# Rapide328smd.net
KiCad netlist of a schematic drawn in EAGLE
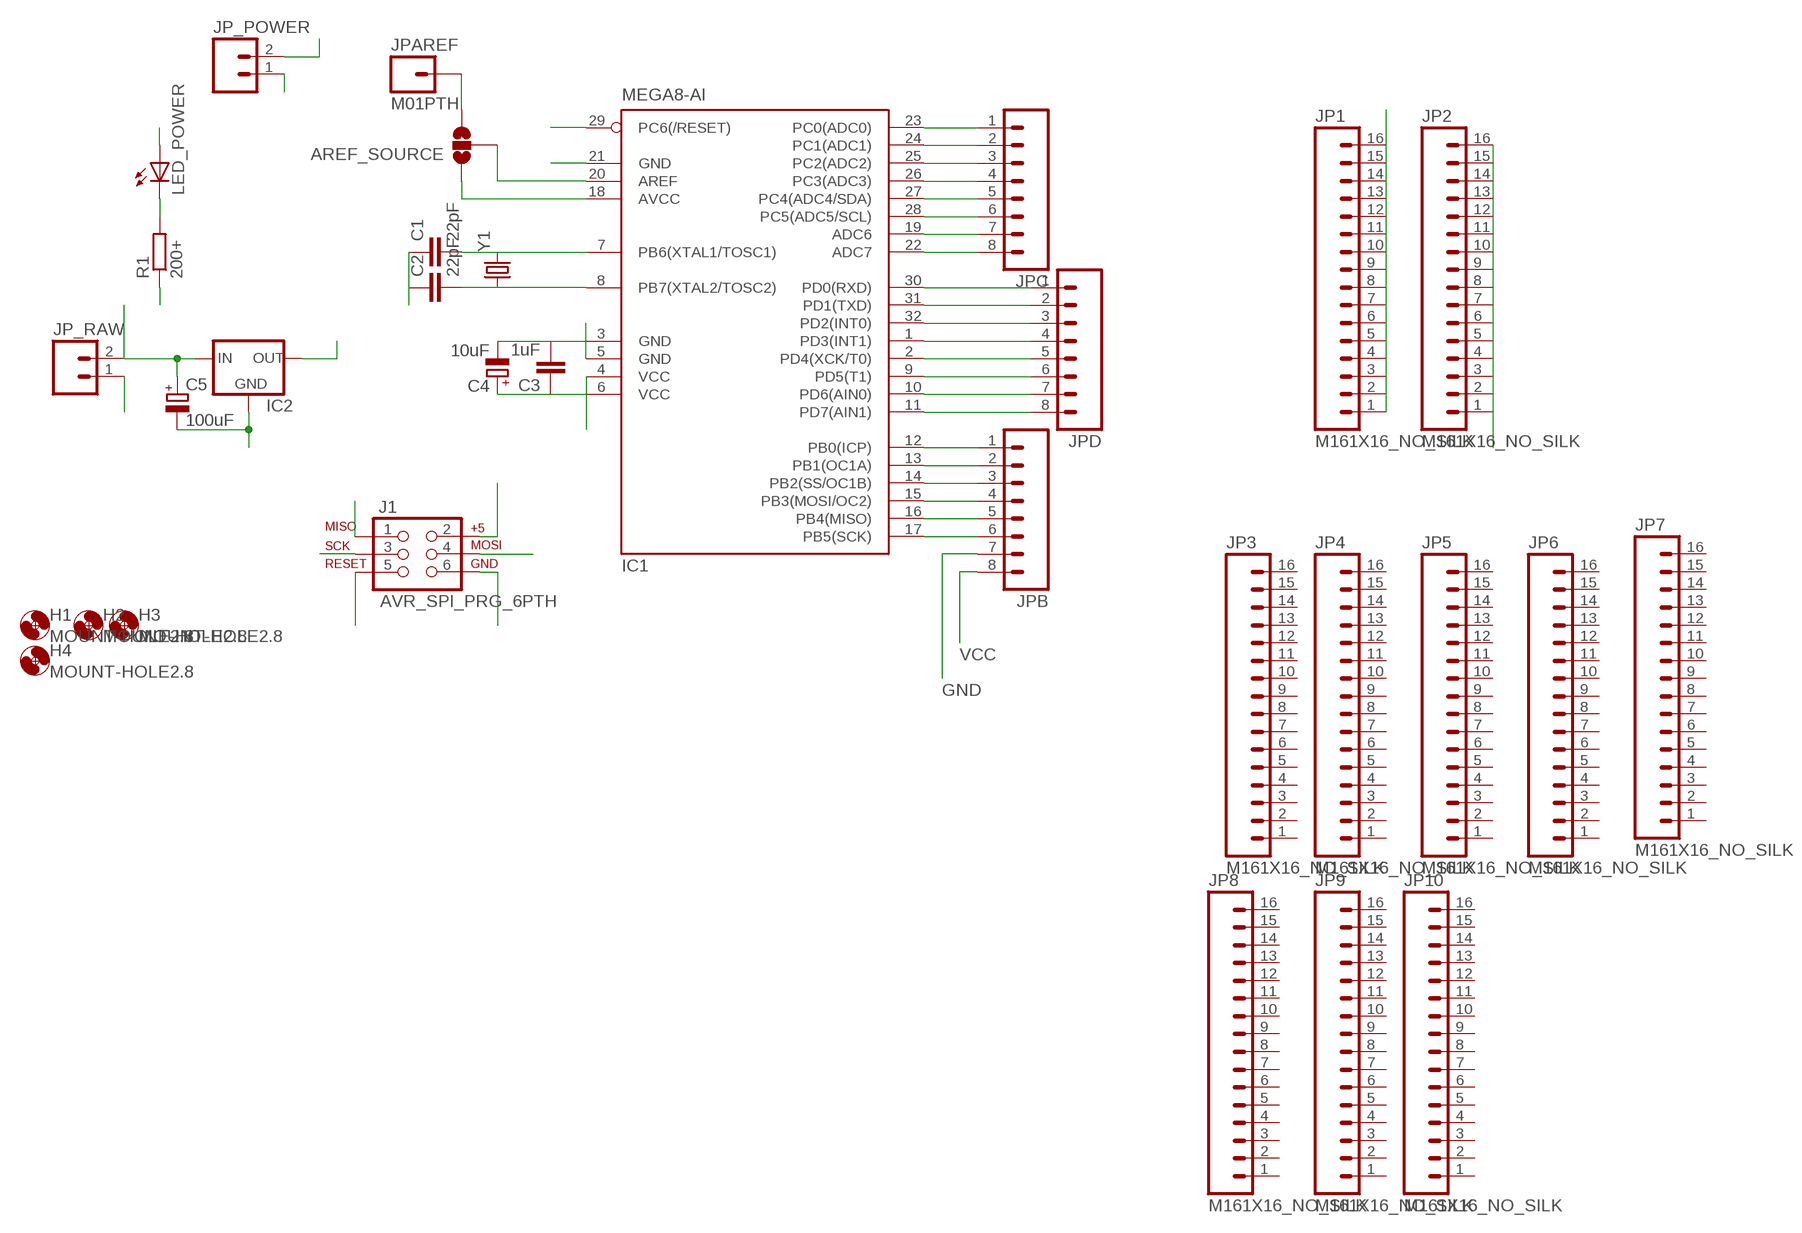
[diagram p0: schematic, sheet 1]

(export (version "E")
  (design (tool "Eeschema 10.0.6"))
  (components
    (comp (ref "AREF_SOURCE")
      (value "SOLDERJUMPER_2WAYPASTE1&2")
      (footprint "eagle-import:SJ_3_PASTE1&2")
      (libsource (lib "eagle-import") (part "SOLDERJUMPER_2WAYPASTE1&2"))
    )
    (comp (ref "C1")
      (value "22pF")
      (footprint "eagle-import:C025-024X044")
      (libsource (lib "eagle-import") (part "C-EU025-024X044"))
    )
    (comp (ref "C2")
      (value "22pF")
      (footprint "eagle-import:C025-024X044")
      (libsource (lib "eagle-import") (part "C-EU025-024X044"))
    )
    (comp (ref "C3")
      (value "1uF")
      (footprint "eagle-import:C025-024X044")
      (libsource (lib "eagle-import") (part "C-EU025-024X044"))
    )
    (comp (ref "C4")
      (value "10uF")
      (footprint "eagle-import:E2-5")
      (libsource (lib "eagle-import") (part "CPOL-EUE2-5"))
    )
    (comp (ref "C5")
      (value "100uF")
      (footprint "eagle-import:E2-5")
      (libsource (lib "eagle-import") (part "CPOL-EUE2-5"))
    )
    (comp (ref "H1")
      (value "MOUNT-HOLE2.8")
      (footprint "eagle-import:2,8")
      (libsource (lib "eagle-import") (part "MOUNT-HOLE2.8"))
    )
    (comp (ref "H2")
      (value "MOUNT-HOLE2.8")
      (footprint "eagle-import:2,8")
      (libsource (lib "eagle-import") (part "MOUNT-HOLE2.8"))
    )
    (comp (ref "H3")
      (value "MOUNT-HOLE2.8")
      (footprint "eagle-import:2,8")
      (libsource (lib "eagle-import") (part "MOUNT-HOLE2.8"))
    )
    (comp (ref "H4")
      (value "MOUNT-HOLE2.8")
      (footprint "eagle-import:2,8")
      (libsource (lib "eagle-import") (part "MOUNT-HOLE2.8"))
    )
    (comp (ref "IC1")
      (value "MEGA8-AI")
      (footprint "eagle-import:TQFP32-08")
      (fields (field (name "MPN") "ATMEGA8-16AU"))
      (libsource (lib "eagle-import") (part "MEGA8-AI"))
    )
    (comp (ref "IC2")
      (value "V_REG_78XXSINK")
      (footprint "eagle-import:TO220-IGO")
      (libsource (lib "eagle-import") (part "V_REG_78XXSINK"))
    )
    (comp (ref "J1")
      (value "AVR_SPI_PRG_6PTH")
      (footprint "eagle-import:2X3")
      (libsource (lib "eagle-import") (part "AVR_SPI_PRG_6PTH"))
    )
    (comp (ref "JP1")
      (value "M161X16_NO_SILK")
      (footprint "eagle-import:1X16_NO_SILK")
      (libsource (lib "eagle-import") (part "M161X16_NO_SILK"))
    )
    (comp (ref "JP2")
      (value "M161X16_NO_SILK")
      (footprint "eagle-import:1X16_NO_SILK")
      (libsource (lib "eagle-import") (part "M161X16_NO_SILK"))
    )
    (comp (ref "JP3")
      (value "M161X16_NO_SILK")
      (footprint "eagle-import:1X16_NO_SILK")
      (libsource (lib "eagle-import") (part "M161X16_NO_SILK"))
    )
    (comp (ref "JP4")
      (value "M161X16_NO_SILK")
      (footprint "eagle-import:1X16_NO_SILK")
      (libsource (lib "eagle-import") (part "M161X16_NO_SILK"))
    )
    (comp (ref "JP5")
      (value "M161X16_NO_SILK")
      (footprint "eagle-import:1X16_NO_SILK")
      (libsource (lib "eagle-import") (part "M161X16_NO_SILK"))
    )
    (comp (ref "JP6")
      (value "M161X16_NO_SILK")
      (footprint "eagle-import:1X16_NO_SILK")
      (libsource (lib "eagle-import") (part "M161X16_NO_SILK"))
    )
    (comp (ref "JP7")
      (value "M161X16_NO_SILK")
      (footprint "eagle-import:1X16_NO_SILK")
      (libsource (lib "eagle-import") (part "M161X16_NO_SILK"))
    )
    (comp (ref "JP8")
      (value "M161X16_NO_SILK")
      (footprint "eagle-import:1X16_NO_SILK")
      (libsource (lib "eagle-import") (part "M161X16_NO_SILK"))
    )
    (comp (ref "JP9")
      (value "M161X16_NO_SILK")
      (footprint "eagle-import:1X16_NO_SILK")
      (libsource (lib "eagle-import") (part "M161X16_NO_SILK"))
    )
    (comp (ref "JP10")
      (value "M161X16_NO_SILK")
      (footprint "eagle-import:1X16_NO_SILK")
      (libsource (lib "eagle-import") (part "M161X16_NO_SILK"))
    )
    (comp (ref "JPAREF")
      (value "M01PTH")
      (footprint "eagle-import:1X01")
      (libsource (lib "eagle-import") (part "M01PTH"))
    )
    (comp (ref "JPB")
      (value "M081X08")
      (footprint "eagle-import:1X08")
      (libsource (lib "eagle-import") (part "M081X08"))
    )
    (comp (ref "JPC")
      (value "M081X08")
      (footprint "eagle-import:1X08")
      (libsource (lib "eagle-import") (part "M081X08"))
    )
    (comp (ref "JPD")
      (value "M081X08")
      (footprint "eagle-import:1X08")
      (libsource (lib "eagle-import") (part "M081X08"))
    )
    (comp (ref "JP_POWER")
      (value "M02PTH3")
      (footprint "eagle-import:1X02_LONGPADS")
      (libsource (lib "eagle-import") (part "M02PTH3"))
    )
    (comp (ref "JP_RAW")
      (value "M02PTH3")
      (footprint "eagle-import:1X02_LONGPADS")
      (libsource (lib "eagle-import") (part "M02PTH3"))
    )
    (comp (ref "LED_POWER")
      (value "LEDKA-3528ASYC")
      (footprint "eagle-import:KA-3528ASYC")
      (libsource (lib "eagle-import") (part "LEDKA-3528ASYC"))
    )
    (comp (ref "R1")
      (value "200+")
      (footprint "eagle-import:0204_7")
      (libsource (lib "eagle-import") (part "R-EU_0204/7"))
    )
    (comp (ref "Y1")
      (value "CRYSTALHC49UV")
      (footprint "eagle-import:HC49U-V")
      (libsource (lib "eagle-import") (part "CRYSTALHC49UV"))
    )
  )
  (nets
    (net (code "1") (name "/GND") (class "Default")
      (node (ref "C1") (pin "1") (pinfunction "1_1") (pintype "passive"))
      (node (ref "C2") (pin "1") (pinfunction "1_1") (pintype "passive"))
      (node (ref "C3") (pin "2") (pinfunction "2_2") (pintype "passive"))
      (node (ref "C4") (pin "-") (pinfunction "-_-") (pintype "passive"))
      (node (ref "C5") (pin "-") (pinfunction "-_-") (pintype "passive"))
      (node (ref "IC1") (pin "21") (pinfunction "GND_21") (pintype "power_in"))
      (node (ref "IC1") (pin "3") (pinfunction "GND_3") (pintype "power_in"))
      (node (ref "IC1") (pin "5") (pinfunction "GND_5") (pintype "power_in"))
      (node (ref "IC2") (pin "GND") (pinfunction "GND_GND") (pintype "input"))
      (node (ref "J1") (pin "6") (pinfunction "6_6") (pintype "passive"))
      (node (ref "JP2") (pin "1") (pinfunction "1_1") (pintype "passive"))
      (node (ref "JP2") (pin "10") (pinfunction "10_10") (pintype "passive"))
      (node (ref "JP2") (pin "11") (pinfunction "11_11") (pintype "passive"))
      (node (ref "JP2") (pin "12") (pinfunction "12_12") (pintype "passive"))
      (node (ref "JP2") (pin "13") (pinfunction "13_13") (pintype "passive"))
      (node (ref "JP2") (pin "14") (pinfunction "14_14") (pintype "passive"))
      (node (ref "JP2") (pin "15") (pinfunction "15_15") (pintype "passive"))
      (node (ref "JP2") (pin "16") (pinfunction "16_16") (pintype "passive"))
      (node (ref "JP2") (pin "2") (pinfunction "2_2") (pintype "passive"))
      (node (ref "JP2") (pin "3") (pinfunction "3_3") (pintype "passive"))
      (node (ref "JP2") (pin "4") (pinfunction "4_4") (pintype "passive"))
      (node (ref "JP2") (pin "5") (pinfunction "5_5") (pintype "passive"))
      (node (ref "JP2") (pin "6") (pinfunction "6_6") (pintype "passive"))
      (node (ref "JP2") (pin "7") (pinfunction "7_7") (pintype "passive"))
      (node (ref "JP2") (pin "8") (pinfunction "8_8") (pintype "passive"))
      (node (ref "JP2") (pin "9") (pinfunction "9_9") (pintype "passive"))
      (node (ref "JPB") (pin "7") (pinfunction "7_7") (pintype "passive"))
      (node (ref "JP_POWER") (pin "1") (pinfunction "1_1") (pintype "passive"))
      (node (ref "JP_RAW") (pin "1") (pinfunction "1_1") (pintype "passive"))
      (node (ref "R1") (pin "1") (pinfunction "1_1") (pintype "passive"))
    )
    (net (code "2") (name "/MISO") (class "Default")
      (node (ref "IC1") (pin "16") (pinfunction "PB4(MISO)_16") (pintype "bidirectional"))
      (node (ref "J1") (pin "1") (pinfunction "1_1") (pintype "passive"))
      (node (ref "JPB") (pin "5") (pinfunction "5_5") (pintype "passive"))
    )
    (net (code "3") (name "/MOSI") (class "Default")
      (node (ref "IC1") (pin "15") (pinfunction "PB3(MOSI/OC2)_15") (pintype "bidirectional"))
      (node (ref "J1") (pin "4") (pinfunction "4_4") (pintype "passive"))
      (node (ref "JPB") (pin "4") (pinfunction "4_4") (pintype "passive"))
    )
    (net (code "4") (name "/RESET") (class "Default")
      (node (ref "IC1") (pin "29") (pinfunction "PC6(/RESET)_29") (pintype "bidirectional"))
      (node (ref "J1") (pin "5") (pinfunction "5_5") (pintype "passive"))
    )
    (net (code "5") (name "/SCK") (class "Default")
      (node (ref "IC1") (pin "17") (pinfunction "PB5(SCK)_17") (pintype "bidirectional"))
      (node (ref "J1") (pin "3") (pinfunction "3_3") (pintype "passive"))
      (node (ref "JPB") (pin "6") (pinfunction "6_6") (pintype "passive"))
    )
    (net (code "6") (name "/VCC") (class "Default")
      (node (ref "AREF_SOURCE") (pin "1") (pinfunction "1_1") (pintype "passive"))
      (node (ref "C3") (pin "1") (pinfunction "1_1") (pintype "passive"))
      (node (ref "C4") (pin "+") (pinfunction "+_+") (pintype "passive"))
      (node (ref "IC1") (pin "18") (pinfunction "AVCC_18") (pintype "power_in"))
      (node (ref "IC1") (pin "4") (pinfunction "VCC_4") (pintype "power_in"))
      (node (ref "IC1") (pin "6") (pinfunction "VCC_6") (pintype "power_in"))
      (node (ref "IC2") (pin "OUT") (pinfunction "OUT_OUT") (pintype "output"))
      (node (ref "J1") (pin "2") (pinfunction "2_2") (pintype "passive"))
      (node (ref "JP1") (pin "1") (pinfunction "1_1") (pintype "passive"))
      (node (ref "JP1") (pin "10") (pinfunction "10_10") (pintype "passive"))
      (node (ref "JP1") (pin "11") (pinfunction "11_11") (pintype "passive"))
      (node (ref "JP1") (pin "12") (pinfunction "12_12") (pintype "passive"))
      (node (ref "JP1") (pin "13") (pinfunction "13_13") (pintype "passive"))
      (node (ref "JP1") (pin "14") (pinfunction "14_14") (pintype "passive"))
      (node (ref "JP1") (pin "15") (pinfunction "15_15") (pintype "passive"))
      (node (ref "JP1") (pin "16") (pinfunction "16_16") (pintype "passive"))
      (node (ref "JP1") (pin "2") (pinfunction "2_2") (pintype "passive"))
      (node (ref "JP1") (pin "3") (pinfunction "3_3") (pintype "passive"))
      (node (ref "JP1") (pin "4") (pinfunction "4_4") (pintype "passive"))
      (node (ref "JP1") (pin "5") (pinfunction "5_5") (pintype "passive"))
      (node (ref "JP1") (pin "6") (pinfunction "6_6") (pintype "passive"))
      (node (ref "JP1") (pin "7") (pinfunction "7_7") (pintype "passive"))
      (node (ref "JP1") (pin "8") (pinfunction "8_8") (pintype "passive"))
      (node (ref "JP1") (pin "9") (pinfunction "9_9") (pintype "passive"))
      (node (ref "JPB") (pin "8") (pinfunction "8_8") (pintype "passive"))
      (node (ref "JP_POWER") (pin "2") (pinfunction "2_2") (pintype "passive"))
      (node (ref "LED_POWER") (pin "A") (pinfunction "A_A") (pintype "passive"))
    )
    (net (code "7") (name "Net-(AREF_SOURCE-Pad3)") (class "Default")
      (node (ref "AREF_SOURCE") (pin "3") (pinfunction "3_3") (pintype "passive"))
      (node (ref "JPAREF") (pin "1") (pinfunction "1_1") (pintype "passive"))
    )
    (net (code "8") (name "Net-(C5-Pad+)") (class "Default")
      (node (ref "C5") (pin "+") (pinfunction "+_+") (pintype "passive"))
      (node (ref "IC2") (pin "IN") (pinfunction "IN_IN") (pintype "input"))
      (node (ref "JP_RAW") (pin "2") (pinfunction "2_2") (pintype "passive"))
    )
    (net (code "9") (name "Net-(IC1-ADC6)") (class "Default")
      (node (ref "IC1") (pin "19") (pinfunction "ADC6_19") (pintype "bidirectional"))
      (node (ref "JPC") (pin "7") (pinfunction "7_7") (pintype "passive"))
    )
    (net (code "10") (name "Net-(IC1-ADC7)") (class "Default")
      (node (ref "IC1") (pin "22") (pinfunction "ADC7_22") (pintype "bidirectional"))
      (node (ref "JPC") (pin "8") (pinfunction "8_8") (pintype "passive"))
    )
    (net (code "11") (name "Net-(IC1-AREF)") (class "Default")
      (node (ref "AREF_SOURCE") (pin "2") (pinfunction "2_2") (pintype "passive"))
      (node (ref "IC1") (pin "20") (pinfunction "AREF_20") (pintype "passive"))
    )
    (net (code "12") (name "Net-(IC1-PB0(ICP))") (class "Default")
      (node (ref "IC1") (pin "12") (pinfunction "PB0(ICP)_12") (pintype "bidirectional"))
      (node (ref "JPB") (pin "1") (pinfunction "1_1") (pintype "passive"))
    )
    (net (code "13") (name "Net-(IC1-PB1(OC1A))") (class "Default")
      (node (ref "IC1") (pin "13") (pinfunction "PB1(OC1A)_13") (pintype "bidirectional"))
      (node (ref "JPB") (pin "2") (pinfunction "2_2") (pintype "passive"))
    )
    (net (code "14") (name "Net-(IC1-PB2(SS{slash}OC1B))") (class "Default")
      (node (ref "IC1") (pin "14") (pinfunction "PB2(SS/OC1B)_14") (pintype "bidirectional"))
      (node (ref "JPB") (pin "3") (pinfunction "3_3") (pintype "passive"))
    )
    (net (code "15") (name "Net-(IC1-PB6(XTAL1{slash}TOSC1))") (class "Default")
      (node (ref "C1") (pin "2") (pinfunction "2_2") (pintype "passive"))
      (node (ref "IC1") (pin "7") (pinfunction "PB6(XTAL1/TOSC1)_7") (pintype "bidirectional"))
      (node (ref "Y1") (pin "2") (pinfunction "2_2") (pintype "passive"))
    )
    (net (code "16") (name "Net-(IC1-PB7(XTAL2{slash}TOSC2))") (class "Default")
      (node (ref "C2") (pin "2") (pinfunction "2_2") (pintype "passive"))
      (node (ref "IC1") (pin "8") (pinfunction "PB7(XTAL2/TOSC2)_8") (pintype "bidirectional"))
      (node (ref "Y1") (pin "1") (pinfunction "1_1") (pintype "passive"))
    )
    (net (code "17") (name "Net-(IC1-PC0(ADC0))") (class "Default")
      (node (ref "IC1") (pin "23") (pinfunction "PC0(ADC0)_23") (pintype "bidirectional"))
      (node (ref "JPC") (pin "1") (pinfunction "1_1") (pintype "passive"))
    )
    (net (code "18") (name "Net-(IC1-PC1(ADC1))") (class "Default")
      (node (ref "IC1") (pin "24") (pinfunction "PC1(ADC1)_24") (pintype "bidirectional"))
      (node (ref "JPC") (pin "2") (pinfunction "2_2") (pintype "passive"))
    )
    (net (code "19") (name "Net-(IC1-PC2(ADC2))") (class "Default")
      (node (ref "IC1") (pin "25") (pinfunction "PC2(ADC2)_25") (pintype "bidirectional"))
      (node (ref "JPC") (pin "3") (pinfunction "3_3") (pintype "passive"))
    )
    (net (code "20") (name "Net-(IC1-PC3(ADC3))") (class "Default")
      (node (ref "IC1") (pin "26") (pinfunction "PC3(ADC3)_26") (pintype "bidirectional"))
      (node (ref "JPC") (pin "4") (pinfunction "4_4") (pintype "passive"))
    )
    (net (code "21") (name "Net-(IC1-PC4(ADC4{slash}SDA))") (class "Default")
      (node (ref "IC1") (pin "27") (pinfunction "PC4(ADC4/SDA)_27") (pintype "bidirectional"))
      (node (ref "JPC") (pin "5") (pinfunction "5_5") (pintype "passive"))
    )
    (net (code "22") (name "Net-(IC1-PC5(ADC5{slash}SCL))") (class "Default")
      (node (ref "IC1") (pin "28") (pinfunction "PC5(ADC5/SCL)_28") (pintype "bidirectional"))
      (node (ref "JPC") (pin "6") (pinfunction "6_6") (pintype "passive"))
    )
    (net (code "23") (name "Net-(IC1-PD0(RXD))") (class "Default")
      (node (ref "IC1") (pin "30") (pinfunction "PD0(RXD)_30") (pintype "bidirectional"))
      (node (ref "JPD") (pin "1") (pinfunction "1_1") (pintype "passive"))
    )
    (net (code "24") (name "Net-(IC1-PD1(TXD))") (class "Default")
      (node (ref "IC1") (pin "31") (pinfunction "PD1(TXD)_31") (pintype "bidirectional"))
      (node (ref "JPD") (pin "2") (pinfunction "2_2") (pintype "passive"))
    )
    (net (code "25") (name "Net-(IC1-PD2(INT0))") (class "Default")
      (node (ref "IC1") (pin "32") (pinfunction "PD2(INT0)_32") (pintype "bidirectional"))
      (node (ref "JPD") (pin "3") (pinfunction "3_3") (pintype "passive"))
    )
    (net (code "26") (name "Net-(IC1-PD3(INT1))") (class "Default")
      (node (ref "IC1") (pin "1") (pinfunction "PD3(INT1)_1") (pintype "bidirectional"))
      (node (ref "JPD") (pin "4") (pinfunction "4_4") (pintype "passive"))
    )
    (net (code "27") (name "Net-(IC1-PD4(XCK{slash}T0))") (class "Default")
      (node (ref "IC1") (pin "2") (pinfunction "PD4(XCK/T0)_2") (pintype "bidirectional"))
      (node (ref "JPD") (pin "5") (pinfunction "5_5") (pintype "passive"))
    )
    (net (code "28") (name "Net-(IC1-PD5(T1))") (class "Default")
      (node (ref "IC1") (pin "9") (pinfunction "PD5(T1)_9") (pintype "bidirectional"))
      (node (ref "JPD") (pin "6") (pinfunction "6_6") (pintype "passive"))
    )
    (net (code "29") (name "Net-(IC1-PD6(AIN0))") (class "Default")
      (node (ref "IC1") (pin "10") (pinfunction "PD6(AIN0)_10") (pintype "bidirectional"))
      (node (ref "JPD") (pin "7") (pinfunction "7_7") (pintype "passive"))
    )
    (net (code "30") (name "Net-(IC1-PD7(AIN1))") (class "Default")
      (node (ref "IC1") (pin "11") (pinfunction "PD7(AIN1)_11") (pintype "bidirectional"))
      (node (ref "JPD") (pin "8") (pinfunction "8_8") (pintype "passive"))
    )
    (net (code "31") (name "Net-(LED_POWER-PadC)") (class "Default")
      (node (ref "LED_POWER") (pin "C") (pinfunction "C_C") (pintype "passive"))
      (node (ref "R1") (pin "2") (pinfunction "2_2") (pintype "passive"))
    )
    (net (code "32") (name "unconnected-(JP3-Pad1)") (class "Default")
      (node (ref "JP3") (pin "1") (pinfunction "1_1") (pintype "passive"))
    )
    (net (code "33") (name "unconnected-(JP3-Pad2)") (class "Default")
      (node (ref "JP3") (pin "2") (pinfunction "2_2") (pintype "passive"))
    )
    (net (code "34") (name "unconnected-(JP3-Pad3)") (class "Default")
      (node (ref "JP3") (pin "3") (pinfunction "3_3") (pintype "passive"))
    )
    (net (code "35") (name "unconnected-(JP3-Pad4)") (class "Default")
      (node (ref "JP3") (pin "4") (pinfunction "4_4") (pintype "passive"))
    )
    (net (code "36") (name "unconnected-(JP3-Pad5)") (class "Default")
      (node (ref "JP3") (pin "5") (pinfunction "5_5") (pintype "passive"))
    )
    (net (code "37") (name "unconnected-(JP3-Pad6)") (class "Default")
      (node (ref "JP3") (pin "6") (pinfunction "6_6") (pintype "passive"))
    )
    (net (code "38") (name "unconnected-(JP3-Pad7)") (class "Default")
      (node (ref "JP3") (pin "7") (pinfunction "7_7") (pintype "passive"))
    )
    (net (code "39") (name "unconnected-(JP3-Pad8)") (class "Default")
      (node (ref "JP3") (pin "8") (pinfunction "8_8") (pintype "passive"))
    )
    (net (code "40") (name "unconnected-(JP3-Pad9)") (class "Default")
      (node (ref "JP3") (pin "9") (pinfunction "9_9") (pintype "passive"))
    )
    (net (code "41") (name "unconnected-(JP3-Pad10)") (class "Default")
      (node (ref "JP3") (pin "10") (pinfunction "10_10") (pintype "passive"))
    )
    (net (code "42") (name "unconnected-(JP3-Pad11)") (class "Default")
      (node (ref "JP3") (pin "11") (pinfunction "11_11") (pintype "passive"))
    )
    (net (code "43") (name "unconnected-(JP3-Pad12)") (class "Default")
      (node (ref "JP3") (pin "12") (pinfunction "12_12") (pintype "passive"))
    )
    (net (code "44") (name "unconnected-(JP3-Pad13)") (class "Default")
      (node (ref "JP3") (pin "13") (pinfunction "13_13") (pintype "passive"))
    )
    (net (code "45") (name "unconnected-(JP3-Pad14)") (class "Default")
      (node (ref "JP3") (pin "14") (pinfunction "14_14") (pintype "passive"))
    )
    (net (code "46") (name "unconnected-(JP3-Pad15)") (class "Default")
      (node (ref "JP3") (pin "15") (pinfunction "15_15") (pintype "passive"))
    )
    (net (code "47") (name "unconnected-(JP3-Pad16)") (class "Default")
      (node (ref "JP3") (pin "16") (pinfunction "16_16") (pintype "passive"))
    )
    (net (code "48") (name "unconnected-(JP4-Pad1)") (class "Default")
      (node (ref "JP4") (pin "1") (pinfunction "1_1") (pintype "passive"))
    )
    (net (code "49") (name "unconnected-(JP4-Pad2)") (class "Default")
      (node (ref "JP4") (pin "2") (pinfunction "2_2") (pintype "passive"))
    )
    (net (code "50") (name "unconnected-(JP4-Pad3)") (class "Default")
      (node (ref "JP4") (pin "3") (pinfunction "3_3") (pintype "passive"))
    )
    (net (code "51") (name "unconnected-(JP4-Pad4)") (class "Default")
      (node (ref "JP4") (pin "4") (pinfunction "4_4") (pintype "passive"))
    )
    (net (code "52") (name "unconnected-(JP4-Pad5)") (class "Default")
      (node (ref "JP4") (pin "5") (pinfunction "5_5") (pintype "passive"))
    )
    (net (code "53") (name "unconnected-(JP4-Pad6)") (class "Default")
      (node (ref "JP4") (pin "6") (pinfunction "6_6") (pintype "passive"))
    )
    (net (code "54") (name "unconnected-(JP4-Pad7)") (class "Default")
      (node (ref "JP4") (pin "7") (pinfunction "7_7") (pintype "passive"))
    )
    (net (code "55") (name "unconnected-(JP4-Pad8)") (class "Default")
      (node (ref "JP4") (pin "8") (pinfunction "8_8") (pintype "passive"))
    )
    (net (code "56") (name "unconnected-(JP4-Pad9)") (class "Default")
      (node (ref "JP4") (pin "9") (pinfunction "9_9") (pintype "passive"))
    )
    (net (code "57") (name "unconnected-(JP4-Pad10)") (class "Default")
      (node (ref "JP4") (pin "10") (pinfunction "10_10") (pintype "passive"))
    )
    (net (code "58") (name "unconnected-(JP4-Pad11)") (class "Default")
      (node (ref "JP4") (pin "11") (pinfunction "11_11") (pintype "passive"))
    )
    (net (code "59") (name "unconnected-(JP4-Pad12)") (class "Default")
      (node (ref "JP4") (pin "12") (pinfunction "12_12") (pintype "passive"))
    )
    (net (code "60") (name "unconnected-(JP4-Pad13)") (class "Default")
      (node (ref "JP4") (pin "13") (pinfunction "13_13") (pintype "passive"))
    )
    (net (code "61") (name "unconnected-(JP4-Pad14)") (class "Default")
      (node (ref "JP4") (pin "14") (pinfunction "14_14") (pintype "passive"))
    )
    (net (code "62") (name "unconnected-(JP4-Pad15)") (class "Default")
      (node (ref "JP4") (pin "15") (pinfunction "15_15") (pintype "passive"))
    )
    (net (code "63") (name "unconnected-(JP4-Pad16)") (class "Default")
      (node (ref "JP4") (pin "16") (pinfunction "16_16") (pintype "passive"))
    )
    (net (code "64") (name "unconnected-(JP5-Pad1)") (class "Default")
      (node (ref "JP5") (pin "1") (pinfunction "1_1") (pintype "passive"))
    )
    (net (code "65") (name "unconnected-(JP5-Pad2)") (class "Default")
      (node (ref "JP5") (pin "2") (pinfunction "2_2") (pintype "passive"))
    )
    (net (code "66") (name "unconnected-(JP5-Pad3)") (class "Default")
      (node (ref "JP5") (pin "3") (pinfunction "3_3") (pintype "passive"))
    )
    (net (code "67") (name "unconnected-(JP5-Pad4)") (class "Default")
      (node (ref "JP5") (pin "4") (pinfunction "4_4") (pintype "passive"))
    )
    (net (code "68") (name "unconnected-(JP5-Pad5)") (class "Default")
      (node (ref "JP5") (pin "5") (pinfunction "5_5") (pintype "passive"))
    )
    (net (code "69") (name "unconnected-(JP5-Pad6)") (class "Default")
      (node (ref "JP5") (pin "6") (pinfunction "6_6") (pintype "passive"))
    )
    (net (code "70") (name "unconnected-(JP5-Pad7)") (class "Default")
      (node (ref "JP5") (pin "7") (pinfunction "7_7") (pintype "passive"))
    )
    (net (code "71") (name "unconnected-(JP5-Pad8)") (class "Default")
      (node (ref "JP5") (pin "8") (pinfunction "8_8") (pintype "passive"))
    )
    (net (code "72") (name "unconnected-(JP5-Pad9)") (class "Default")
      (node (ref "JP5") (pin "9") (pinfunction "9_9") (pintype "passive"))
    )
    (net (code "73") (name "unconnected-(JP5-Pad10)") (class "Default")
      (node (ref "JP5") (pin "10") (pinfunction "10_10") (pintype "passive"))
    )
    (net (code "74") (name "unconnected-(JP5-Pad11)") (class "Default")
      (node (ref "JP5") (pin "11") (pinfunction "11_11") (pintype "passive"))
    )
    (net (code "75") (name "unconnected-(JP5-Pad12)") (class "Default")
      (node (ref "JP5") (pin "12") (pinfunction "12_12") (pintype "passive"))
    )
    (net (code "76") (name "unconnected-(JP5-Pad13)") (class "Default")
      (node (ref "JP5") (pin "13") (pinfunction "13_13") (pintype "passive"))
    )
    (net (code "77") (name "unconnected-(JP5-Pad14)") (class "Default")
      (node (ref "JP5") (pin "14") (pinfunction "14_14") (pintype "passive"))
    )
    (net (code "78") (name "unconnected-(JP5-Pad15)") (class "Default")
      (node (ref "JP5") (pin "15") (pinfunction "15_15") (pintype "passive"))
    )
    (net (code "79") (name "unconnected-(JP5-Pad16)") (class "Default")
      (node (ref "JP5") (pin "16") (pinfunction "16_16") (pintype "passive"))
    )
    (net (code "80") (name "unconnected-(JP6-Pad1)") (class "Default")
      (node (ref "JP6") (pin "1") (pinfunction "1_1") (pintype "passive"))
    )
    (net (code "81") (name "unconnected-(JP6-Pad2)") (class "Default")
      (node (ref "JP6") (pin "2") (pinfunction "2_2") (pintype "passive"))
    )
    (net (code "82") (name "unconnected-(JP6-Pad3)") (class "Default")
      (node (ref "JP6") (pin "3") (pinfunction "3_3") (pintype "passive"))
    )
    (net (code "83") (name "unconnected-(JP6-Pad4)") (class "Default")
      (node (ref "JP6") (pin "4") (pinfunction "4_4") (pintype "passive"))
    )
    (net (code "84") (name "unconnected-(JP6-Pad5)") (class "Default")
      (node (ref "JP6") (pin "5") (pinfunction "5_5") (pintype "passive"))
    )
    (net (code "85") (name "unconnected-(JP6-Pad6)") (class "Default")
      (node (ref "JP6") (pin "6") (pinfunction "6_6") (pintype "passive"))
    )
    (net (code "86") (name "unconnected-(JP6-Pad7)") (class "Default")
      (node (ref "JP6") (pin "7") (pinfunction "7_7") (pintype "passive"))
    )
    (net (code "87") (name "unconnected-(JP6-Pad8)") (class "Default")
      (node (ref "JP6") (pin "8") (pinfunction "8_8") (pintype "passive"))
    )
    (net (code "88") (name "unconnected-(JP6-Pad9)") (class "Default")
      (node (ref "JP6") (pin "9") (pinfunction "9_9") (pintype "passive"))
    )
    (net (code "89") (name "unconnected-(JP6-Pad10)") (class "Default")
      (node (ref "JP6") (pin "10") (pinfunction "10_10") (pintype "passive"))
    )
    (net (code "90") (name "unconnected-(JP6-Pad11)") (class "Default")
      (node (ref "JP6") (pin "11") (pinfunction "11_11") (pintype "passive"))
    )
    (net (code "91") (name "unconnected-(JP6-Pad12)") (class "Default")
      (node (ref "JP6") (pin "12") (pinfunction "12_12") (pintype "passive"))
    )
    (net (code "92") (name "unconnected-(JP6-Pad13)") (class "Default")
      (node (ref "JP6") (pin "13") (pinfunction "13_13") (pintype "passive"))
    )
    (net (code "93") (name "unconnected-(JP6-Pad14)") (class "Default")
      (node (ref "JP6") (pin "14") (pinfunction "14_14") (pintype "passive"))
    )
    (net (code "94") (name "unconnected-(JP6-Pad15)") (class "Default")
      (node (ref "JP6") (pin "15") (pinfunction "15_15") (pintype "passive"))
    )
    (net (code "95") (name "unconnected-(JP6-Pad16)") (class "Default")
      (node (ref "JP6") (pin "16") (pinfunction "16_16") (pintype "passive"))
    )
    (net (code "96") (name "unconnected-(JP7-Pad1)") (class "Default")
      (node (ref "JP7") (pin "1") (pinfunction "1_1") (pintype "passive"))
    )
    (net (code "97") (name "unconnected-(JP7-Pad2)") (class "Default")
      (node (ref "JP7") (pin "2") (pinfunction "2_2") (pintype "passive"))
    )
    (net (code "98") (name "unconnected-(JP7-Pad3)") (class "Default")
      (node (ref "JP7") (pin "3") (pinfunction "3_3") (pintype "passive"))
    )
    (net (code "99") (name "unconnected-(JP7-Pad4)") (class "Default")
      (node (ref "JP7") (pin "4") (pinfunction "4_4") (pintype "passive"))
    )
    (net (code "100") (name "unconnected-(JP7-Pad5)") (class "Default")
      (node (ref "JP7") (pin "5") (pinfunction "5_5") (pintype "passive"))
    )
    (net (code "101") (name "unconnected-(JP7-Pad6)") (class "Default")
      (node (ref "JP7") (pin "6") (pinfunction "6_6") (pintype "passive"))
    )
    (net (code "102") (name "unconnected-(JP7-Pad7)") (class "Default")
      (node (ref "JP7") (pin "7") (pinfunction "7_7") (pintype "passive"))
    )
    (net (code "103") (name "unconnected-(JP7-Pad8)") (class "Default")
      (node (ref "JP7") (pin "8") (pinfunction "8_8") (pintype "passive"))
    )
    (net (code "104") (name "unconnected-(JP7-Pad9)") (class "Default")
      (node (ref "JP7") (pin "9") (pinfunction "9_9") (pintype "passive"))
    )
    (net (code "105") (name "unconnected-(JP7-Pad10)") (class "Default")
      (node (ref "JP7") (pin "10") (pinfunction "10_10") (pintype "passive"))
    )
    (net (code "106") (name "unconnected-(JP7-Pad11)") (class "Default")
      (node (ref "JP7") (pin "11") (pinfunction "11_11") (pintype "passive"))
    )
    (net (code "107") (name "unconnected-(JP7-Pad12)") (class "Default")
      (node (ref "JP7") (pin "12") (pinfunction "12_12") (pintype "passive"))
    )
    (net (code "108") (name "unconnected-(JP7-Pad13)") (class "Default")
      (node (ref "JP7") (pin "13") (pinfunction "13_13") (pintype "passive"))
    )
    (net (code "109") (name "unconnected-(JP7-Pad14)") (class "Default")
      (node (ref "JP7") (pin "14") (pinfunction "14_14") (pintype "passive"))
    )
    (net (code "110") (name "unconnected-(JP7-Pad15)") (class "Default")
      (node (ref "JP7") (pin "15") (pinfunction "15_15") (pintype "passive"))
    )
    (net (code "111") (name "unconnected-(JP7-Pad16)") (class "Default")
      (node (ref "JP7") (pin "16") (pinfunction "16_16") (pintype "passive"))
    )
    (net (code "112") (name "unconnected-(JP8-Pad1)") (class "Default")
      (node (ref "JP8") (pin "1") (pinfunction "1_1") (pintype "passive"))
    )
    (net (code "113") (name "unconnected-(JP8-Pad2)") (class "Default")
      (node (ref "JP8") (pin "2") (pinfunction "2_2") (pintype "passive"))
    )
    (net (code "114") (name "unconnected-(JP8-Pad3)") (class "Default")
      (node (ref "JP8") (pin "3") (pinfunction "3_3") (pintype "passive"))
    )
    (net (code "115") (name "unconnected-(JP8-Pad4)") (class "Default")
      (node (ref "JP8") (pin "4") (pinfunction "4_4") (pintype "passive"))
    )
    (net (code "116") (name "unconnected-(JP8-Pad5)") (class "Default")
      (node (ref "JP8") (pin "5") (pinfunction "5_5") (pintype "passive"))
    )
    (net (code "117") (name "unconnected-(JP8-Pad6)") (class "Default")
      (node (ref "JP8") (pin "6") (pinfunction "6_6") (pintype "passive"))
    )
    (net (code "118") (name "unconnected-(JP8-Pad7)") (class "Default")
      (node (ref "JP8") (pin "7") (pinfunction "7_7") (pintype "passive"))
    )
    (net (code "119") (name "unconnected-(JP8-Pad8)") (class "Default")
      (node (ref "JP8") (pin "8") (pinfunction "8_8") (pintype "passive"))
    )
    (net (code "120") (name "unconnected-(JP8-Pad9)") (class "Default")
      (node (ref "JP8") (pin "9") (pinfunction "9_9") (pintype "passive"))
    )
    (net (code "121") (name "unconnected-(JP8-Pad10)") (class "Default")
      (node (ref "JP8") (pin "10") (pinfunction "10_10") (pintype "passive"))
    )
    (net (code "122") (name "unconnected-(JP8-Pad11)") (class "Default")
      (node (ref "JP8") (pin "11") (pinfunction "11_11") (pintype "passive"))
    )
    (net (code "123") (name "unconnected-(JP8-Pad12)") (class "Default")
      (node (ref "JP8") (pin "12") (pinfunction "12_12") (pintype "passive"))
    )
    (net (code "124") (name "unconnected-(JP8-Pad13)") (class "Default")
      (node (ref "JP8") (pin "13") (pinfunction "13_13") (pintype "passive"))
    )
    (net (code "125") (name "unconnected-(JP8-Pad14)") (class "Default")
      (node (ref "JP8") (pin "14") (pinfunction "14_14") (pintype "passive"))
    )
    (net (code "126") (name "unconnected-(JP8-Pad15)") (class "Default")
      (node (ref "JP8") (pin "15") (pinfunction "15_15") (pintype "passive"))
    )
    (net (code "127") (name "unconnected-(JP8-Pad16)") (class "Default")
      (node (ref "JP8") (pin "16") (pinfunction "16_16") (pintype "passive"))
    )
    (net (code "128") (name "unconnected-(JP9-Pad1)") (class "Default")
      (node (ref "JP9") (pin "1") (pinfunction "1_1") (pintype "passive"))
    )
    (net (code "129") (name "unconnected-(JP9-Pad2)") (class "Default")
      (node (ref "JP9") (pin "2") (pinfunction "2_2") (pintype "passive"))
    )
    (net (code "130") (name "unconnected-(JP9-Pad3)") (class "Default")
      (node (ref "JP9") (pin "3") (pinfunction "3_3") (pintype "passive"))
    )
    (net (code "131") (name "unconnected-(JP9-Pad4)") (class "Default")
      (node (ref "JP9") (pin "4") (pinfunction "4_4") (pintype "passive"))
    )
    (net (code "132") (name "unconnected-(JP9-Pad5)") (class "Default")
      (node (ref "JP9") (pin "5") (pinfunction "5_5") (pintype "passive"))
    )
    (net (code "133") (name "unconnected-(JP9-Pad6)") (class "Default")
      (node (ref "JP9") (pin "6") (pinfunction "6_6") (pintype "passive"))
    )
    (net (code "134") (name "unconnected-(JP9-Pad7)") (class "Default")
      (node (ref "JP9") (pin "7") (pinfunction "7_7") (pintype "passive"))
    )
    (net (code "135") (name "unconnected-(JP9-Pad8)") (class "Default")
      (node (ref "JP9") (pin "8") (pinfunction "8_8") (pintype "passive"))
    )
    (net (code "136") (name "unconnected-(JP9-Pad9)") (class "Default")
      (node (ref "JP9") (pin "9") (pinfunction "9_9") (pintype "passive"))
    )
    (net (code "137") (name "unconnected-(JP9-Pad10)") (class "Default")
      (node (ref "JP9") (pin "10") (pinfunction "10_10") (pintype "passive"))
    )
    (net (code "138") (name "unconnected-(JP9-Pad11)") (class "Default")
      (node (ref "JP9") (pin "11") (pinfunction "11_11") (pintype "passive"))
    )
    (net (code "139") (name "unconnected-(JP9-Pad12)") (class "Default")
      (node (ref "JP9") (pin "12") (pinfunction "12_12") (pintype "passive"))
    )
    (net (code "140") (name "unconnected-(JP9-Pad13)") (class "Default")
      (node (ref "JP9") (pin "13") (pinfunction "13_13") (pintype "passive"))
    )
    (net (code "141") (name "unconnected-(JP9-Pad14)") (class "Default")
      (node (ref "JP9") (pin "14") (pinfunction "14_14") (pintype "passive"))
    )
    (net (code "142") (name "unconnected-(JP9-Pad15)") (class "Default")
      (node (ref "JP9") (pin "15") (pinfunction "15_15") (pintype "passive"))
    )
    (net (code "143") (name "unconnected-(JP9-Pad16)") (class "Default")
      (node (ref "JP9") (pin "16") (pinfunction "16_16") (pintype "passive"))
    )
    (net (code "144") (name "unconnected-(JP10-Pad1)") (class "Default")
      (node (ref "JP10") (pin "1") (pinfunction "1_1") (pintype "passive"))
    )
    (net (code "145") (name "unconnected-(JP10-Pad2)") (class "Default")
      (node (ref "JP10") (pin "2") (pinfunction "2_2") (pintype "passive"))
    )
    (net (code "146") (name "unconnected-(JP10-Pad3)") (class "Default")
      (node (ref "JP10") (pin "3") (pinfunction "3_3") (pintype "passive"))
    )
    (net (code "147") (name "unconnected-(JP10-Pad4)") (class "Default")
      (node (ref "JP10") (pin "4") (pinfunction "4_4") (pintype "passive"))
    )
    (net (code "148") (name "unconnected-(JP10-Pad5)") (class "Default")
      (node (ref "JP10") (pin "5") (pinfunction "5_5") (pintype "passive"))
    )
    (net (code "149") (name "unconnected-(JP10-Pad6)") (class "Default")
      (node (ref "JP10") (pin "6") (pinfunction "6_6") (pintype "passive"))
    )
    (net (code "150") (name "unconnected-(JP10-Pad7)") (class "Default")
      (node (ref "JP10") (pin "7") (pinfunction "7_7") (pintype "passive"))
    )
    (net (code "151") (name "unconnected-(JP10-Pad8)") (class "Default")
      (node (ref "JP10") (pin "8") (pinfunction "8_8") (pintype "passive"))
    )
    (net (code "152") (name "unconnected-(JP10-Pad9)") (class "Default")
      (node (ref "JP10") (pin "9") (pinfunction "9_9") (pintype "passive"))
    )
    (net (code "153") (name "unconnected-(JP10-Pad10)") (class "Default")
      (node (ref "JP10") (pin "10") (pinfunction "10_10") (pintype "passive"))
    )
    (net (code "154") (name "unconnected-(JP10-Pad11)") (class "Default")
      (node (ref "JP10") (pin "11") (pinfunction "11_11") (pintype "passive"))
    )
    (net (code "155") (name "unconnected-(JP10-Pad12)") (class "Default")
      (node (ref "JP10") (pin "12") (pinfunction "12_12") (pintype "passive"))
    )
    (net (code "156") (name "unconnected-(JP10-Pad13)") (class "Default")
      (node (ref "JP10") (pin "13") (pinfunction "13_13") (pintype "passive"))
    )
    (net (code "157") (name "unconnected-(JP10-Pad14)") (class "Default")
      (node (ref "JP10") (pin "14") (pinfunction "14_14") (pintype "passive"))
    )
    (net (code "158") (name "unconnected-(JP10-Pad15)") (class "Default")
      (node (ref "JP10") (pin "15") (pinfunction "15_15") (pintype "passive"))
    )
    (net (code "159") (name "unconnected-(JP10-Pad16)") (class "Default")
      (node (ref "JP10") (pin "16") (pinfunction "16_16") (pintype "passive"))
    )
  )
)
